# Servo.net
KiCad netlist of a schematic drawn in EAGLE
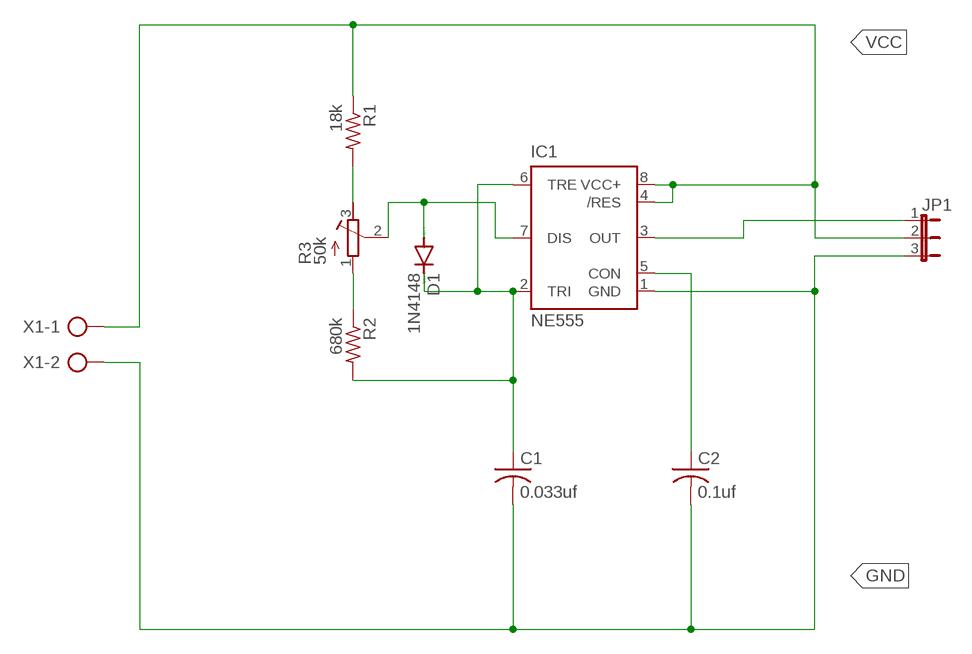
[diagram p0: schematic, sheet 1]

(export (version "E")
  (design (tool "Eeschema 10.0.6"))
  (components
    (comp (ref "C1")
      (value "0.033uf")
      (footprint "eagle-import:C025-024X044")
      (libsource (lib "eagle-import") (part "C-US025-024X044"))
    )
    (comp (ref "C2")
      (value "0.1uf")
      (footprint "eagle-import:C025-024X044")
      (libsource (lib "eagle-import") (part "C-US025-024X044"))
    )
    (comp (ref "D1")
      (value "1N4148")
      (footprint "eagle-import:DO35-10")
      (libsource (lib "eagle-import") (part "1N4148DO35-10"))
    )
    (comp (ref "IC1")
      (value "NE555")
      (footprint "eagle-import:DIL-08")
      (fields (field (name "MF") "Arrow Electronics") (field (name "MPN") "NE555N"))
      (libsource (lib "eagle-import") (part "NE555"))
    )
    (comp (ref "JP1")
      (value "JP2W")
      (footprint "eagle-import:JP2W")
      (libsource (lib "eagle-import") (part "JP2W"))
    )
    (comp (ref "R1")
      (value "18k")
      (footprint "eagle-import:0204_7")
      (libsource (lib "eagle-import") (part "R-US_0204/7"))
    )
    (comp (ref "R2")
      (value "680k")
      (footprint "eagle-import:0204_7")
      (libsource (lib "eagle-import") (part "R-US_0204/7"))
    )
    (comp (ref "R3")
      (value "50k")
      (footprint "eagle-import:RTRIM64W")
      (libsource (lib "eagle-import") (part "R-TRIMM64W"))
    )
    (comp (ref "X1")
      (value "AK500/2")
      (footprint "eagle-import:AK500_2")
      (libsource (lib "eagle-import") (part "AK500/2"))
    )
  )
  (nets
    (net (code "1") (name "GND") (class "Default")
      (node (ref "C1") (pin "2") (pinfunction "2_2") (pintype "passive"))
      (node (ref "C2") (pin "2") (pinfunction "2_2") (pintype "passive"))
      (node (ref "IC1") (pin "1") (pinfunction "GND_1") (pintype "power_in"))
      (node (ref "JP1") (pin "3") (pinfunction "3_3") (pintype "passive"))
      (node (ref "X1") (pin "2") (pinfunction "KL_2") (pintype "passive"))
    )
    (net (code "2") (name "Net-(IC1-CON)") (class "Default")
      (node (ref "C2") (pin "1") (pinfunction "1_1") (pintype "passive"))
      (node (ref "IC1") (pin "5") (pinfunction "CON_5") (pintype "input"))
    )
    (net (code "3") (name "Net-(IC1-DIS)") (class "Default")
      (node (ref "D1") (pin "A") (pinfunction "A_A") (pintype "passive"))
      (node (ref "IC1") (pin "7") (pinfunction "DIS_7") (pintype "input"))
      (node (ref "R3") (pin "2") (pinfunction "S_2") (pintype "passive"))
    )
    (net (code "4") (name "Net-(IC1-OUT)") (class "Default")
      (node (ref "IC1") (pin "3") (pinfunction "OUT_3") (pintype "output"))
      (node (ref "JP1") (pin "1") (pinfunction "1_1") (pintype "passive"))
    )
    (net (code "5") (name "Net-(IC1-TRE)") (class "Default")
      (node (ref "C1") (pin "1") (pinfunction "1_1") (pintype "passive"))
      (node (ref "D1") (pin "C") (pinfunction "C_C") (pintype "passive"))
      (node (ref "IC1") (pin "2") (pinfunction "TRI_2") (pintype "input"))
      (node (ref "IC1") (pin "6") (pinfunction "TRE_6") (pintype "input"))
      (node (ref "R2") (pin "2") (pinfunction "2_2") (pintype "passive"))
    )
    (net (code "6") (name "Net-(R3-A)") (class "Default")
      (node (ref "R2") (pin "1") (pinfunction "1_1") (pintype "passive"))
      (node (ref "R3") (pin "1") (pinfunction "A_1") (pintype "passive"))
    )
    (net (code "7") (name "Net-(R3-E)") (class "Default")
      (node (ref "R1") (pin "2") (pinfunction "2_2") (pintype "passive"))
      (node (ref "R3") (pin "3") (pinfunction "E_3") (pintype "passive"))
    )
    (net (code "8") (name "VCC") (class "Default")
      (node (ref "IC1") (pin "4") (pinfunction "/RES_4") (pintype "input"))
      (node (ref "IC1") (pin "8") (pinfunction "VCC+_8") (pintype "power_in"))
      (node (ref "JP1") (pin "2") (pinfunction "2_2") (pintype "passive"))
      (node (ref "R1") (pin "1") (pinfunction "1_1") (pintype "passive"))
      (node (ref "X1") (pin "1") (pinfunction "KL_1") (pintype "passive"))
    )
  )
)
